# tritiled_v31_xpe.net
KiCad netlist of a schematic drawn in EAGLE
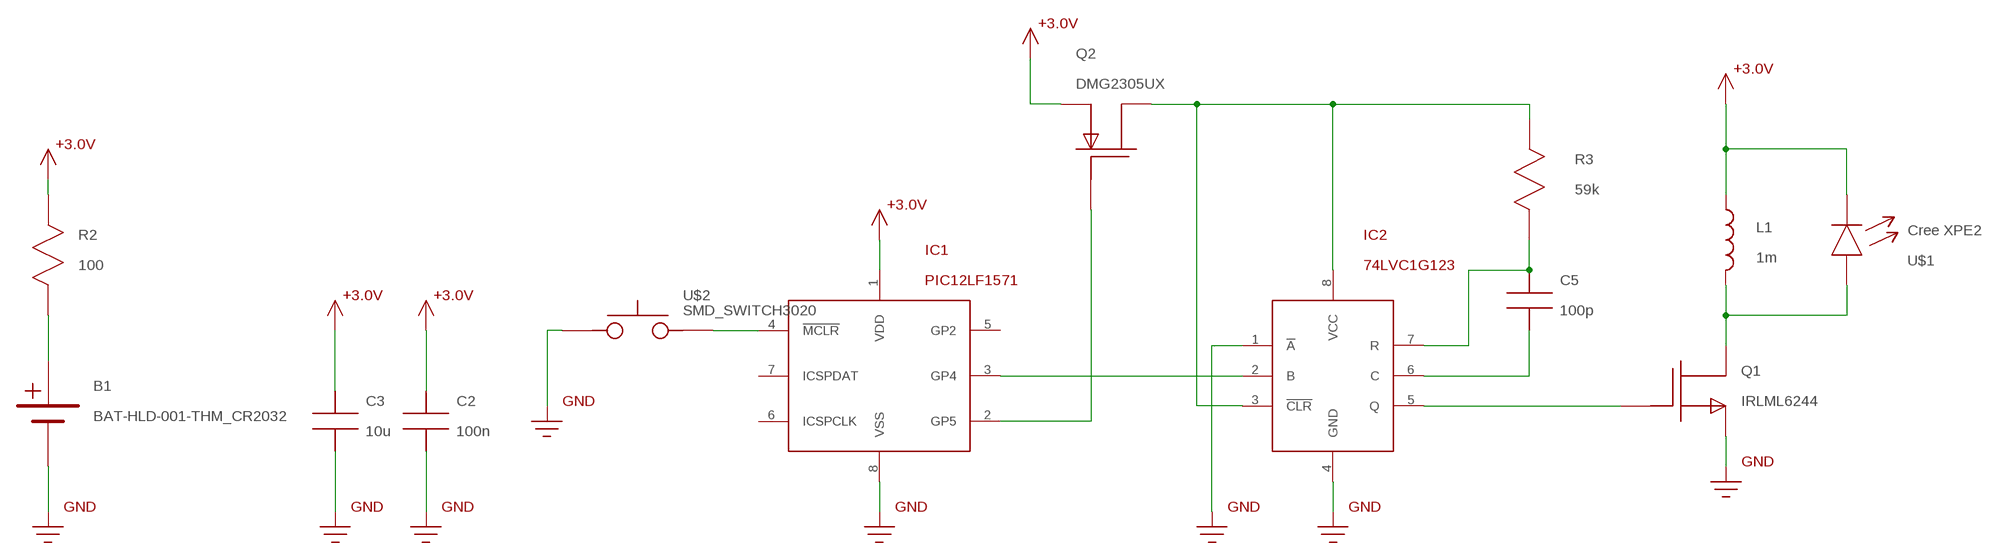
[diagram p0: schematic, sheet 1]

(export (version "E")
  (design (tool "Eeschema 10.0.6"))
  (components
    (comp (ref "B1")
      (value "BAT-HLD-001-THM_CR2032")
      (footprint "eagle-import:CR2032_BAT-HLD-001-THM")
      (libsource (lib "eagle-import") (part "BAT-HLD-001-THM_CR2032"))
    )
    (comp (ref "C2")
      (value "100n")
      (footprint "eagle-import:0805")
      (libsource (lib "eagle-import") (part "C0805"))
    )
    (comp (ref "C3")
      (value "10u")
      (footprint "eagle-import:1206")
      (libsource (lib "eagle-import") (part "C1206"))
    )
    (comp (ref "C5")
      (value "100p")
      (footprint "eagle-import:C0603")
      (libsource (lib "eagle-import") (part "C0603"))
    )
    (comp (ref "IC1")
      (value "PIC12LF1571")
      (footprint "eagle-import:SOIC8")
      (libsource (lib "eagle-import") (part "PIC12LF1571"))
    )
    (comp (ref "IC2")
      (value "74LVC1G123")
      (footprint "eagle-import:SM8")
      (libsource (lib "eagle-import") (part "74LVC1G123"))
    )
    (comp (ref "L1")
      (value "1m")
      (footprint "eagle-import:SRR6028_INDUCTOR")
      (libsource (lib "eagle-import") (part "SRR6028_INDUCTOR"))
    )
    (comp (ref "Q1")
      (value "IRLML6244")
      (footprint "eagle-import:SOT-23")
      (libsource (lib "eagle-import") (part "ZXMN3B01FSOT23"))
    )
    (comp (ref "Q2")
      (value "DMG2305UX")
      (footprint "eagle-import:SOT-23")
      (libsource (lib "eagle-import") (part "DMG2305UXSOT23"))
    )
    (comp (ref "R2")
      (value "100")
      (footprint "eagle-import:R1206")
      (libsource (lib "eagle-import") (part "R1206"))
    )
    (comp (ref "R3")
      (value "59k")
      (footprint "eagle-import:R0603")
      (libsource (lib "eagle-import") (part "R0603"))
    )
    (comp (ref "U$1")
      (value "Cree XPE2")
      (footprint "eagle-import:CREE_XPE_LED")
      (libsource (lib "eagle-import") (part "LEDCREE_XPE"))
    )
    (comp (ref "U$2")
      (value "SMD_SWITCH3020")
      (footprint "eagle-import:SWITCH_3020")
      (libsource (lib "eagle-import") (part "SMD_SWITCH3020"))
    )
  )
  (nets
    (net (code "1") (name "+3.0V") (class "Default")
      (node (ref "C2") (pin "P$1") (pinfunction "P$1_P$1") (pintype "bidirectional"))
      (node (ref "C3") (pin "P$1") (pinfunction "P$1_P$1") (pintype "bidirectional"))
      (node (ref "IC1") (pin "1") (pinfunction "VDD_1") (pintype "bidirectional"))
      (node (ref "L1") (pin "P$1") (pinfunction "1_P$1") (pintype "passive"))
      (node (ref "Q2") (pin "2") (pinfunction "S_2") (pintype "bidirectional"))
      (node (ref "R2") (pin "P$1") (pinfunction "P$1_P$1") (pintype "bidirectional"))
      (node (ref "U$1") (pin "C") (pinfunction "C_C") (pintype "bidirectional"))
    )
    (net (code "2") (name "GND") (class "Default")
      (node (ref "B1") (pin "GND") (pinfunction "0V_GND") (pintype "power_in"))
      (node (ref "C2") (pin "P$2") (pinfunction "P$2_P$2") (pintype "bidirectional"))
      (node (ref "C3") (pin "P$2") (pinfunction "P$2_P$2") (pintype "bidirectional"))
      (node (ref "IC1") (pin "8") (pinfunction "VSS_8") (pintype "bidirectional"))
      (node (ref "IC2") (pin "1") (pinfunction "~{A}_1") (pintype "bidirectional"))
      (node (ref "IC2") (pin "4") (pinfunction "GND_4") (pintype "bidirectional"))
      (node (ref "Q1") (pin "2") (pinfunction "S_2") (pintype "bidirectional"))
      (node (ref "U$2") (pin "A") (pinfunction "P$1_A") (pintype "bidirectional"))
    )
    (net (code "3") (name "Net-(B1-+V-Pad+V@1)") (class "Default")
      (node (ref "B1") (pin "+V@1") (pinfunction "+V_+V@1") (pintype "power_in"))
      (node (ref "B1") (pin "+V@2") (pinfunction "+V_+V@2") (pintype "power_in"))
      (node (ref "B1") (pin "+V@3") (pinfunction "+V_+V@3") (pintype "power_in"))
      (node (ref "B1") (pin "+V@4") (pinfunction "+V_+V@4") (pintype "power_in"))
      (node (ref "R2") (pin "P$2") (pinfunction "P$2_P$2") (pintype "bidirectional"))
    )
    (net (code "4") (name "Net-(IC1-GP4)") (class "Default")
      (node (ref "IC1") (pin "3") (pinfunction "GP4_3") (pintype "bidirectional"))
      (node (ref "IC2") (pin "2") (pinfunction "B_2") (pintype "bidirectional"))
    )
    (net (code "5") (name "Net-(IC1-GP5)") (class "Default")
      (node (ref "IC1") (pin "2") (pinfunction "GP5_2") (pintype "bidirectional"))
      (node (ref "Q2") (pin "1") (pinfunction "G_1") (pintype "bidirectional"))
    )
    (net (code "6") (name "Net-(IC1-~{MCLR})") (class "Default")
      (node (ref "IC1") (pin "4") (pinfunction "~{MCLR}_4") (pintype "bidirectional"))
      (node (ref "U$2") (pin "B") (pinfunction "P$2_B") (pintype "bidirectional"))
    )
    (net (code "7") (name "Net-(IC2-C)") (class "Default")
      (node (ref "C5") (pin "P$2") (pinfunction "P$2_P$2") (pintype "bidirectional"))
      (node (ref "IC2") (pin "6") (pinfunction "C_6") (pintype "bidirectional"))
    )
    (net (code "8") (name "Net-(IC2-Q)") (class "Default")
      (node (ref "IC2") (pin "5") (pinfunction "Q_5") (pintype "bidirectional"))
      (node (ref "Q1") (pin "1") (pinfunction "G_1") (pintype "bidirectional"))
    )
    (net (code "9") (name "Net-(IC2-R)") (class "Default")
      (node (ref "C5") (pin "P$1") (pinfunction "P$1_P$1") (pintype "bidirectional"))
      (node (ref "IC2") (pin "7") (pinfunction "R_7") (pintype "bidirectional"))
      (node (ref "R3") (pin "P$1") (pinfunction "P$1_P$1") (pintype "bidirectional"))
    )
    (net (code "10") (name "Net-(IC2-VCC)") (class "Default")
      (node (ref "IC2") (pin "3") (pinfunction "~{CLR}_3") (pintype "bidirectional"))
      (node (ref "IC2") (pin "8") (pinfunction "VCC_8") (pintype "bidirectional"))
      (node (ref "Q2") (pin "3") (pinfunction "D_3") (pintype "bidirectional"))
      (node (ref "R3") (pin "P$2") (pinfunction "P$2_P$2") (pintype "bidirectional"))
    )
    (net (code "11") (name "Net-(L1-2)") (class "Default")
      (node (ref "L1") (pin "P$2") (pinfunction "2_P$2") (pintype "passive"))
      (node (ref "Q1") (pin "3") (pinfunction "D_3") (pintype "bidirectional"))
      (node (ref "U$1") (pin "A") (pinfunction "A_A") (pintype "bidirectional"))
    )
    (net (code "12") (name "unconnected-(IC1-GP2-Pad5)") (class "Default")
      (node (ref "IC1") (pin "5") (pinfunction "GP2_5") (pintype "bidirectional"))
    )
    (net (code "13") (name "unconnected-(IC1-ICSPCLK-Pad6)") (class "Default")
      (node (ref "IC1") (pin "6") (pinfunction "ICSPCLK_6") (pintype "bidirectional"))
    )
    (net (code "14") (name "unconnected-(IC1-ICSPDAT-Pad7)") (class "Default")
      (node (ref "IC1") (pin "7") (pinfunction "ICSPDAT_7") (pintype "bidirectional"))
    )
  )
)
